# v3pow_2_4v7.net
KiCad netlist of a schematic drawn in EAGLE
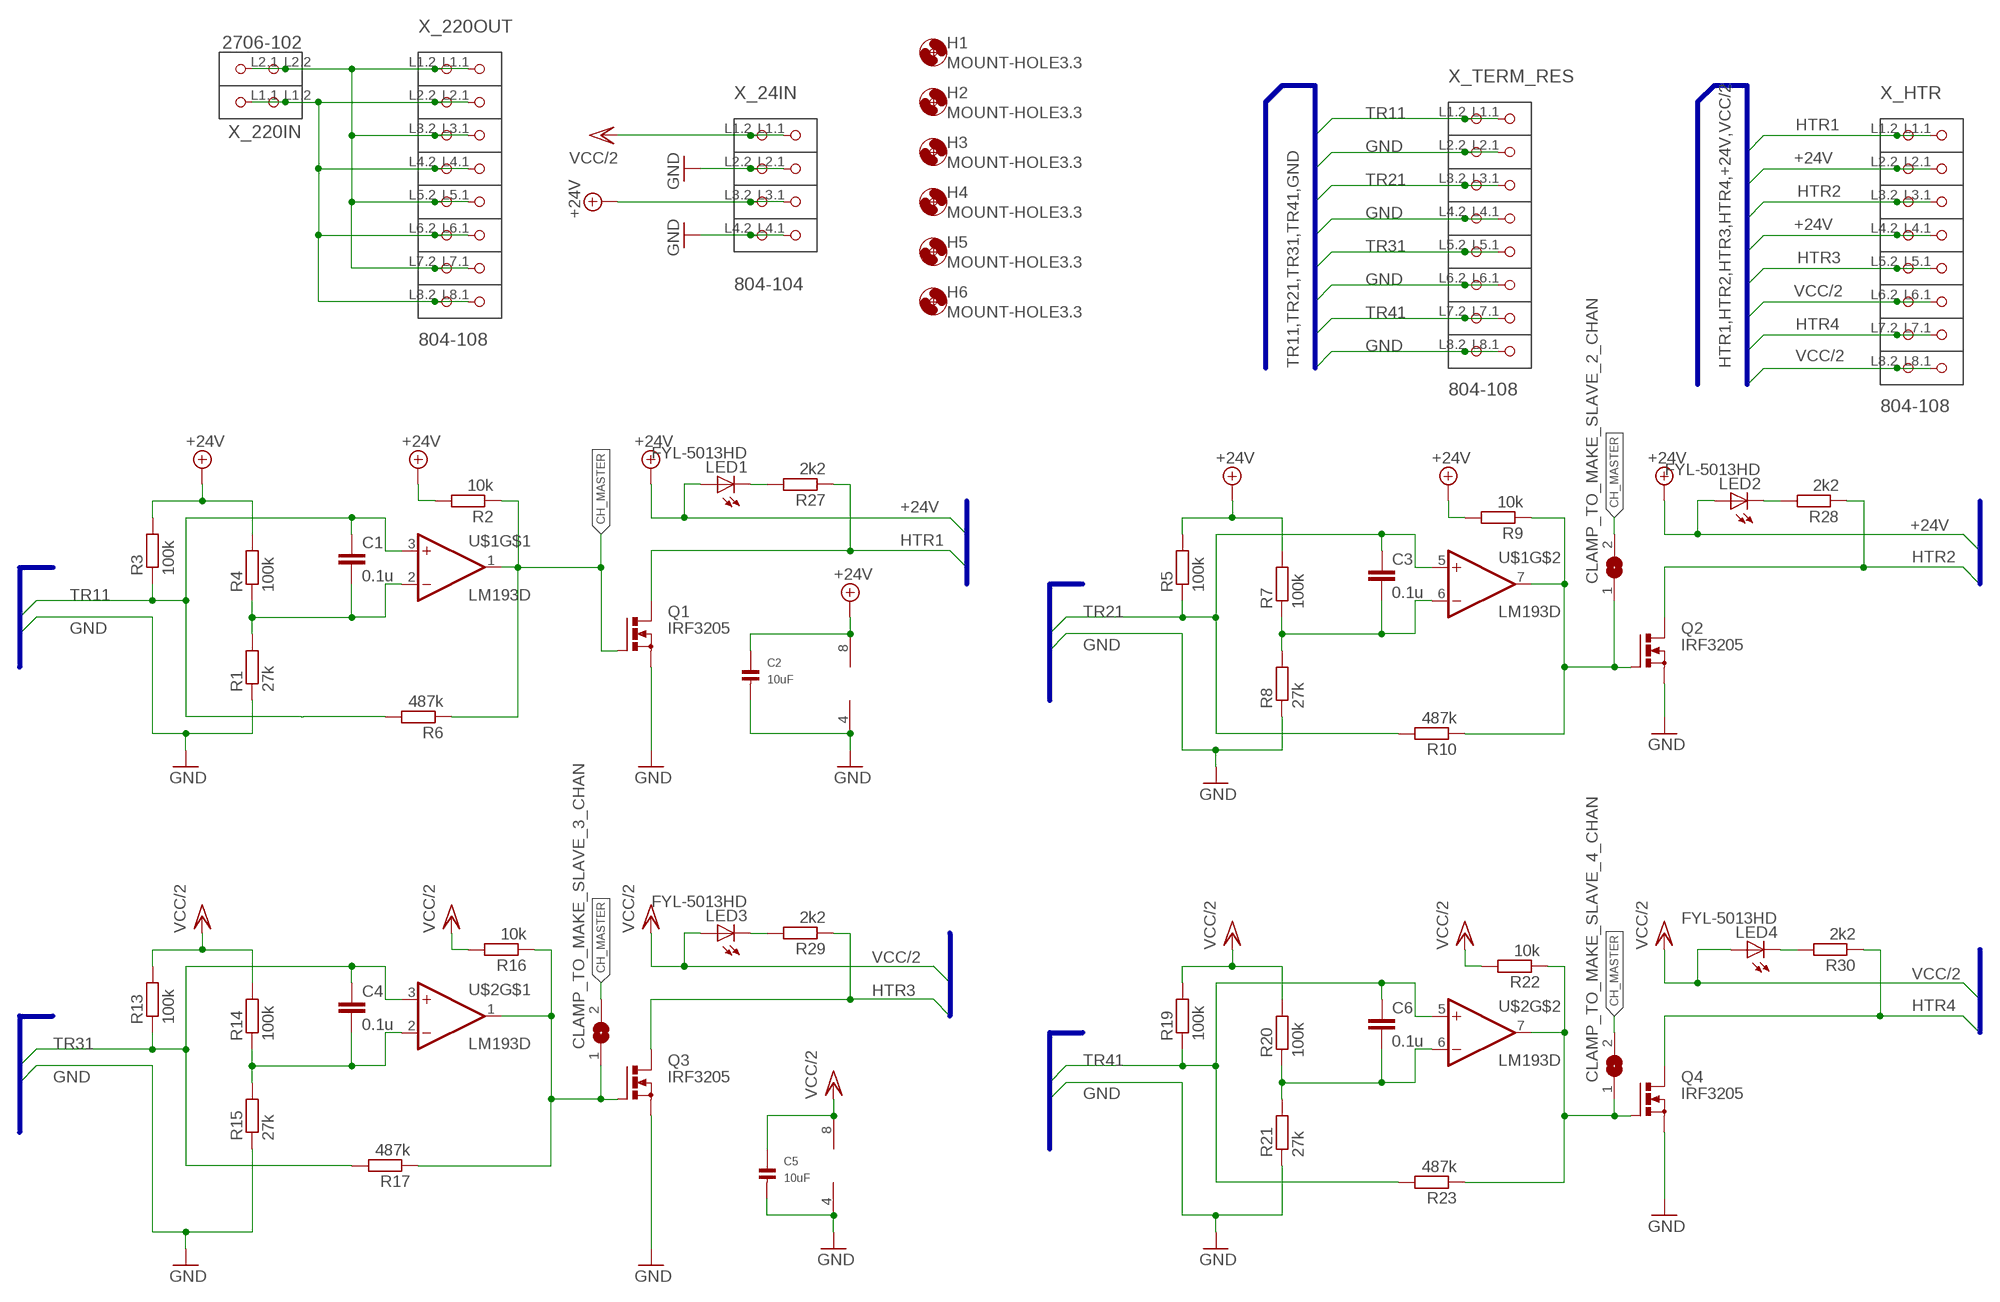
[diagram p0: schematic, sheet 1]

(export (version "E")
  (design (tool "Eeschema 10.0.6"))
  (components
    (comp (ref "C1")
      (value "0.1u")
      (footprint "eagle-import:C0805")
      (libsource (lib "eagle-import") (part "C-EUC0805"))
    )
    (comp (ref "C2")
      (value "10uF")
      (footprint "eagle-import:1206")
      (libsource (lib "eagle-import") (part "CAP_CERAMIC1206"))
    )
    (comp (ref "C3")
      (value "0.1u")
      (footprint "eagle-import:C0805")
      (libsource (lib "eagle-import") (part "C-EUC0805"))
    )
    (comp (ref "C4")
      (value "0.1u")
      (footprint "eagle-import:C0805")
      (libsource (lib "eagle-import") (part "C-EUC0805"))
    )
    (comp (ref "C5")
      (value "10uF")
      (footprint "eagle-import:1206")
      (libsource (lib "eagle-import") (part "CAP_CERAMIC1206"))
    )
    (comp (ref "C6")
      (value "0.1u")
      (footprint "eagle-import:C0805")
      (libsource (lib "eagle-import") (part "C-EUC0805"))
    )
    (comp (ref "CLAMP_TO_MAKE_SLAVE_2_CHAN")
      (value "SJ")
      (footprint "eagle-import:SJ")
      (libsource (lib "eagle-import") (part "SJ"))
    )
    (comp (ref "CLAMP_TO_MAKE_SLAVE_3_CHAN")
      (value "SJ")
      (footprint "eagle-import:SJ")
      (libsource (lib "eagle-import") (part "SJ"))
    )
    (comp (ref "CLAMP_TO_MAKE_SLAVE_4_CHAN")
      (value "SJ")
      (footprint "eagle-import:SJ")
      (libsource (lib "eagle-import") (part "SJ"))
    )
    (comp (ref "H1")
      (value "MOUNT-HOLE3.3")
      (footprint "eagle-import:3,3")
      (libsource (lib "eagle-import") (part "MOUNT-HOLE3.3"))
    )
    (comp (ref "H2")
      (value "MOUNT-HOLE3.3")
      (footprint "eagle-import:3,3")
      (libsource (lib "eagle-import") (part "MOUNT-HOLE3.3"))
    )
    (comp (ref "H3")
      (value "MOUNT-HOLE3.3")
      (footprint "eagle-import:3,3")
      (libsource (lib "eagle-import") (part "MOUNT-HOLE3.3"))
    )
    (comp (ref "H4")
      (value "MOUNT-HOLE3.3")
      (footprint "eagle-import:3,3")
      (libsource (lib "eagle-import") (part "MOUNT-HOLE3.3"))
    )
    (comp (ref "H5")
      (value "MOUNT-HOLE3.3")
      (footprint "eagle-import:3,3")
      (libsource (lib "eagle-import") (part "MOUNT-HOLE3.3"))
    )
    (comp (ref "H6")
      (value "MOUNT-HOLE3.3")
      (footprint "eagle-import:3,3")
      (libsource (lib "eagle-import") (part "MOUNT-HOLE3.3"))
    )
    (comp (ref "LED1")
      (value "FYL-5013HD")
      (footprint "eagle-import:LED5MM")
      (libsource (lib "eagle-import") (part "LED5MM"))
    )
    (comp (ref "LED2")
      (value "FYL-5013HD")
      (footprint "eagle-import:LED5MM")
      (libsource (lib "eagle-import") (part "LED5MM"))
    )
    (comp (ref "LED3")
      (value "FYL-5013HD")
      (footprint "eagle-import:LED5MM")
      (libsource (lib "eagle-import") (part "LED5MM"))
    )
    (comp (ref "LED4")
      (value "FYL-5013HD")
      (footprint "eagle-import:LED5MM")
      (libsource (lib "eagle-import") (part "LED5MM"))
    )
    (comp (ref "Q1")
      (value "IRF3205")
      (footprint "eagle-import:TO220BV")
      (libsource (lib "eagle-import") (part "PMOSFET_NTO220BV"))
    )
    (comp (ref "Q2")
      (value "IRF3205")
      (footprint "eagle-import:TO220BV")
      (libsource (lib "eagle-import") (part "PMOSFET_NTO220BV"))
    )
    (comp (ref "Q3")
      (value "IRF3205")
      (footprint "eagle-import:TO220BV")
      (libsource (lib "eagle-import") (part "PMOSFET_NTO220BV"))
    )
    (comp (ref "Q4")
      (value "IRF3205")
      (footprint "eagle-import:TO220BV")
      (libsource (lib "eagle-import") (part "PMOSFET_NTO220BV"))
    )
    (comp (ref "R1")
      (value "27k")
      (footprint "eagle-import:M0805")
      (libsource (lib "eagle-import") (part "R-EU_M0805"))
    )
    (comp (ref "R2")
      (value "10k")
      (footprint "eagle-import:M0805")
      (libsource (lib "eagle-import") (part "R-EU_M0805"))
    )
    (comp (ref "R3")
      (value "100k")
      (footprint "eagle-import:M0805")
      (libsource (lib "eagle-import") (part "R-EU_M0805"))
    )
    (comp (ref "R4")
      (value "100k")
      (footprint "eagle-import:M0805")
      (libsource (lib "eagle-import") (part "R-EU_M0805"))
    )
    (comp (ref "R5")
      (value "100k")
      (footprint "eagle-import:M0805")
      (libsource (lib "eagle-import") (part "R-EU_M0805"))
    )
    (comp (ref "R6")
      (value "487k")
      (footprint "eagle-import:M0805")
      (libsource (lib "eagle-import") (part "R-EU_M0805"))
    )
    (comp (ref "R7")
      (value "100k")
      (footprint "eagle-import:M0805")
      (libsource (lib "eagle-import") (part "R-EU_M0805"))
    )
    (comp (ref "R8")
      (value "27k")
      (footprint "eagle-import:M0805")
      (libsource (lib "eagle-import") (part "R-EU_M0805"))
    )
    (comp (ref "R9")
      (value "10k")
      (footprint "eagle-import:M0805")
      (libsource (lib "eagle-import") (part "R-EU_M0805"))
    )
    (comp (ref "R10")
      (value "487k")
      (footprint "eagle-import:M0805")
      (libsource (lib "eagle-import") (part "R-EU_M0805"))
    )
    (comp (ref "R13")
      (value "100k")
      (footprint "eagle-import:M0805")
      (libsource (lib "eagle-import") (part "R-EU_M0805"))
    )
    (comp (ref "R14")
      (value "100k")
      (footprint "eagle-import:M0805")
      (libsource (lib "eagle-import") (part "R-EU_M0805"))
    )
    (comp (ref "R15")
      (value "27k")
      (footprint "eagle-import:M0805")
      (libsource (lib "eagle-import") (part "R-EU_M0805"))
    )
    (comp (ref "R16")
      (value "10k")
      (footprint "eagle-import:M0805")
      (libsource (lib "eagle-import") (part "R-EU_M0805"))
    )
    (comp (ref "R17")
      (value "487k")
      (footprint "eagle-import:M0805")
      (libsource (lib "eagle-import") (part "R-EU_M0805"))
    )
    (comp (ref "R19")
      (value "100k")
      (footprint "eagle-import:M0805")
      (libsource (lib "eagle-import") (part "R-EU_M0805"))
    )
    (comp (ref "R20")
      (value "100k")
      (footprint "eagle-import:M0805")
      (libsource (lib "eagle-import") (part "R-EU_M0805"))
    )
    (comp (ref "R21")
      (value "27k")
      (footprint "eagle-import:M0805")
      (libsource (lib "eagle-import") (part "R-EU_M0805"))
    )
    (comp (ref "R22")
      (value "10k")
      (footprint "eagle-import:M0805")
      (libsource (lib "eagle-import") (part "R-EU_M0805"))
    )
    (comp (ref "R23")
      (value "487k")
      (footprint "eagle-import:M0805")
      (libsource (lib "eagle-import") (part "R-EU_M0805"))
    )
    (comp (ref "R27")
      (value "2k2")
      (footprint "eagle-import:M0805")
      (libsource (lib "eagle-import") (part "R-EU_M0805"))
    )
    (comp (ref "R28")
      (value "2k2")
      (footprint "eagle-import:M0805")
      (libsource (lib "eagle-import") (part "R-EU_M0805"))
    )
    (comp (ref "R29")
      (value "2k2")
      (footprint "eagle-import:M0805")
      (libsource (lib "eagle-import") (part "R-EU_M0805"))
    )
    (comp (ref "R30")
      (value "2k2")
      (footprint "eagle-import:M0805")
      (libsource (lib "eagle-import") (part "R-EU_M0805"))
    )
    (comp (ref "U$1")
      (value "LM193D")
      (footprint "eagle-import:SO08")
      (libsource (lib "eagle-import") (part "LM193D"))
    )
    (comp (ref "U$2")
      (value "LM193D")
      (footprint "eagle-import:SO08")
      (libsource (lib "eagle-import") (part "LM193D"))
    )
    (comp (ref "X_24IN")
      (value "804-104")
      (footprint "eagle-import:P-804-104")
      (libsource (lib "eagle-import") (part "804-104"))
    )
    (comp (ref "X_220IN")
      (value "2706-102")
      (footprint "eagle-import:P-2706-102")
      (libsource (lib "eagle-import") (part "2706-102"))
    )
    (comp (ref "X_220OUT")
      (value "804-108")
      (footprint "eagle-import:P-804-108")
      (libsource (lib "eagle-import") (part "804-108"))
    )
    (comp (ref "X_HTR")
      (value "804-108")
      (footprint "eagle-import:P-804-108")
      (libsource (lib "eagle-import") (part "804-108"))
    )
    (comp (ref "X_TERM_RES")
      (value "804-108")
      (footprint "eagle-import:P-804-108")
      (libsource (lib "eagle-import") (part "804-108"))
    )
  )
  (nets
    (net (code "5") (name "+24V") (class "Default")
      (node (ref "C2") (pin "1") (pinfunction "P$1_1") (pintype "passive"))
      (node (ref "LED1") (pin "A") (pinfunction "A_A") (pintype "passive"))
      (node (ref "LED2") (pin "A") (pinfunction "A_A") (pintype "passive"))
      (node (ref "R2") (pin "2") (pinfunction "2_2") (pintype "passive"))
      (node (ref "R3") (pin "2") (pinfunction "2_2") (pintype "passive"))
      (node (ref "R4") (pin "2") (pinfunction "2_2") (pintype "passive"))
      (node (ref "R5") (pin "2") (pinfunction "2_2") (pintype "passive"))
      (node (ref "R7") (pin "2") (pinfunction "2_2") (pintype "passive"))
      (node (ref "R9") (pin "2") (pinfunction "2_2") (pintype "passive"))
      (node (ref "U$1") (pin "8") (pinfunction "V+_8") (pintype "power_in"))
      (node (ref "X_24IN") (pin "L3.1") (pinfunction "P3.1_L3.1") (pintype "bidirectional"))
      (node (ref "X_24IN") (pin "L3.2") (pinfunction "P3.2_L3.2") (pintype "bidirectional"))
      (node (ref "X_HTR") (pin "L2.1") (pinfunction "P2.1_L2.1") (pintype "bidirectional"))
      (node (ref "X_HTR") (pin "L2.2") (pinfunction "P2.2_L2.2") (pintype "bidirectional"))
      (node (ref "X_HTR") (pin "L4.1") (pinfunction "P4.1_L4.1") (pintype "bidirectional"))
      (node (ref "X_HTR") (pin "L4.2") (pinfunction "P4.2_L4.2") (pintype "bidirectional"))
    )
    (net (code "6") (name "/HTR1") (class "Default")
      (node (ref "Q1") (pin "D") (pinfunction "D_D") (pintype "passive"))
      (node (ref "R27") (pin "1") (pinfunction "1_1") (pintype "passive"))
      (node (ref "X_HTR") (pin "L1.1") (pinfunction "P1.1_L1.1") (pintype "bidirectional"))
      (node (ref "X_HTR") (pin "L1.2") (pinfunction "P1.2_L1.2") (pintype "bidirectional"))
    )
    (net (code "7") (name "/HTR2") (class "Default")
      (node (ref "Q2") (pin "D") (pinfunction "D_D") (pintype "passive"))
      (node (ref "R28") (pin "1") (pinfunction "1_1") (pintype "passive"))
      (node (ref "X_HTR") (pin "L3.1") (pinfunction "P3.1_L3.1") (pintype "bidirectional"))
      (node (ref "X_HTR") (pin "L3.2") (pinfunction "P3.2_L3.2") (pintype "bidirectional"))
    )
    (net (code "8") (name "/HTR3") (class "Default")
      (node (ref "Q3") (pin "D") (pinfunction "D_D") (pintype "passive"))
      (node (ref "R29") (pin "1") (pinfunction "1_1") (pintype "passive"))
      (node (ref "X_HTR") (pin "L5.1") (pinfunction "P5.1_L5.1") (pintype "bidirectional"))
      (node (ref "X_HTR") (pin "L5.2") (pinfunction "P5.2_L5.2") (pintype "bidirectional"))
    )
    (net (code "9") (name "/HTR4") (class "Default")
      (node (ref "Q4") (pin "D") (pinfunction "D_D") (pintype "passive"))
      (node (ref "R30") (pin "1") (pinfunction "1_1") (pintype "passive"))
      (node (ref "X_HTR") (pin "L7.1") (pinfunction "P7.1_L7.1") (pintype "bidirectional"))
      (node (ref "X_HTR") (pin "L7.2") (pinfunction "P7.2_L7.2") (pintype "bidirectional"))
    )
    (net (code "10") (name "/TR11") (class "Default")
      (node (ref "C1") (pin "1") (pinfunction "1_1") (pintype "passive"))
      (node (ref "R3") (pin "1") (pinfunction "1_1") (pintype "passive"))
      (node (ref "R6") (pin "2") (pinfunction "2_2") (pintype "passive"))
      (node (ref "U$1") (pin "3") (pinfunction "+IN_3") (pintype "input"))
      (node (ref "X_TERM_RES") (pin "L1.1") (pinfunction "P1.1_L1.1") (pintype "bidirectional"))
      (node (ref "X_TERM_RES") (pin "L1.2") (pinfunction "P1.2_L1.2") (pintype "bidirectional"))
    )
    (net (code "11") (name "/TR21") (class "Default")
      (node (ref "C3") (pin "1") (pinfunction "1_1") (pintype "passive"))
      (node (ref "R10") (pin "2") (pinfunction "2_2") (pintype "passive"))
      (node (ref "R5") (pin "1") (pinfunction "1_1") (pintype "passive"))
      (node (ref "U$1") (pin "5") (pinfunction "+IN_5") (pintype "input"))
      (node (ref "X_TERM_RES") (pin "L3.1") (pinfunction "P3.1_L3.1") (pintype "bidirectional"))
      (node (ref "X_TERM_RES") (pin "L3.2") (pinfunction "P3.2_L3.2") (pintype "bidirectional"))
    )
    (net (code "12") (name "/TR31") (class "Default")
      (node (ref "C4") (pin "1") (pinfunction "1_1") (pintype "passive"))
      (node (ref "R13") (pin "1") (pinfunction "1_1") (pintype "passive"))
      (node (ref "R17") (pin "2") (pinfunction "2_2") (pintype "passive"))
      (node (ref "U$2") (pin "3") (pinfunction "+IN_3") (pintype "input"))
      (node (ref "X_TERM_RES") (pin "L5.1") (pinfunction "P5.1_L5.1") (pintype "bidirectional"))
      (node (ref "X_TERM_RES") (pin "L5.2") (pinfunction "P5.2_L5.2") (pintype "bidirectional"))
    )
    (net (code "13") (name "/TR41") (class "Default")
      (node (ref "C6") (pin "1") (pinfunction "1_1") (pintype "passive"))
      (node (ref "R19") (pin "1") (pinfunction "1_1") (pintype "passive"))
      (node (ref "R23") (pin "2") (pinfunction "2_2") (pintype "passive"))
      (node (ref "U$2") (pin "5") (pinfunction "+IN_5") (pintype "input"))
      (node (ref "X_TERM_RES") (pin "L7.1") (pinfunction "P7.1_L7.1") (pintype "bidirectional"))
      (node (ref "X_TERM_RES") (pin "L7.2") (pinfunction "P7.2_L7.2") (pintype "bidirectional"))
    )
    (net (code "17") (name "CH_MASTER") (class "Default")
      (node (ref "CLAMP_TO_MAKE_SLAVE_2_CHAN") (pin "2") (pinfunction "2_2") (pintype "passive"))
      (node (ref "CLAMP_TO_MAKE_SLAVE_3_CHAN") (pin "2") (pinfunction "2_2") (pintype "passive"))
      (node (ref "CLAMP_TO_MAKE_SLAVE_4_CHAN") (pin "2") (pinfunction "2_2") (pintype "passive"))
      (node (ref "Q1") (pin "G") (pinfunction "G_G") (pintype "passive"))
      (node (ref "R2") (pin "1") (pinfunction "1_1") (pintype "passive"))
      (node (ref "R6") (pin "1") (pinfunction "1_1") (pintype "passive"))
      (node (ref "U$1") (pin "1") (pinfunction "OUT_1") (pintype "output"))
    )
    (net (code "18") (name "GND") (class "Default")
      (node (ref "C2") (pin "2") (pinfunction "P$2_2") (pintype "passive"))
      (node (ref "C5") (pin "2") (pinfunction "P$2_2") (pintype "passive"))
      (node (ref "Q1") (pin "S") (pinfunction "S_S") (pintype "passive"))
      (node (ref "Q2") (pin "S") (pinfunction "S_S") (pintype "passive"))
      (node (ref "Q3") (pin "S") (pinfunction "S_S") (pintype "passive"))
      (node (ref "Q4") (pin "S") (pinfunction "S_S") (pintype "passive"))
      (node (ref "R1") (pin "1") (pinfunction "1_1") (pintype "passive"))
      (node (ref "R15") (pin "1") (pinfunction "1_1") (pintype "passive"))
      (node (ref "R21") (pin "1") (pinfunction "1_1") (pintype "passive"))
      (node (ref "R8") (pin "1") (pinfunction "1_1") (pintype "passive"))
      (node (ref "U$1") (pin "4") (pinfunction "V-_4") (pintype "power_in"))
      (node (ref "U$2") (pin "4") (pinfunction "V-_4") (pintype "power_in"))
      (node (ref "X_24IN") (pin "L2.1") (pinfunction "P2.1_L2.1") (pintype "bidirectional"))
      (node (ref "X_24IN") (pin "L2.2") (pinfunction "P2.2_L2.2") (pintype "bidirectional"))
      (node (ref "X_24IN") (pin "L4.1") (pinfunction "P4.1_L4.1") (pintype "bidirectional"))
      (node (ref "X_24IN") (pin "L4.2") (pinfunction "P4.2_L4.2") (pintype "bidirectional"))
      (node (ref "X_TERM_RES") (pin "L2.1") (pinfunction "P2.1_L2.1") (pintype "bidirectional"))
      (node (ref "X_TERM_RES") (pin "L2.2") (pinfunction "P2.2_L2.2") (pintype "bidirectional"))
      (node (ref "X_TERM_RES") (pin "L4.1") (pinfunction "P4.1_L4.1") (pintype "bidirectional"))
      (node (ref "X_TERM_RES") (pin "L4.2") (pinfunction "P4.2_L4.2") (pintype "bidirectional"))
      (node (ref "X_TERM_RES") (pin "L6.1") (pinfunction "P6.1_L6.1") (pintype "bidirectional"))
      (node (ref "X_TERM_RES") (pin "L6.2") (pinfunction "P6.2_L6.2") (pintype "bidirectional"))
      (node (ref "X_TERM_RES") (pin "L8.1") (pinfunction "P8.1_L8.1") (pintype "bidirectional"))
      (node (ref "X_TERM_RES") (pin "L8.2") (pinfunction "P8.2_L8.2") (pintype "bidirectional"))
    )
    (net (code "19") (name "Net-(LED1-C)") (class "Default")
      (node (ref "LED1") (pin "K") (pinfunction "C_K") (pintype "passive"))
      (node (ref "R27") (pin "2") (pinfunction "2_2") (pintype "passive"))
    )
    (net (code "20") (name "Net-(LED2-C)") (class "Default")
      (node (ref "LED2") (pin "K") (pinfunction "C_K") (pintype "passive"))
      (node (ref "R28") (pin "2") (pinfunction "2_2") (pintype "passive"))
    )
    (net (code "21") (name "Net-(LED3-C)") (class "Default")
      (node (ref "LED3") (pin "K") (pinfunction "C_K") (pintype "passive"))
      (node (ref "R29") (pin "2") (pinfunction "2_2") (pintype "passive"))
    )
    (net (code "22") (name "Net-(LED4-C)") (class "Default")
      (node (ref "LED4") (pin "K") (pinfunction "C_K") (pintype "passive"))
      (node (ref "R30") (pin "2") (pinfunction "2_2") (pintype "passive"))
    )
    (net (code "23") (name "Net-(U$1A--IN)") (class "Default")
      (node (ref "C1") (pin "2") (pinfunction "2_2") (pintype "passive"))
      (node (ref "R1") (pin "2") (pinfunction "2_2") (pintype "passive"))
      (node (ref "R4") (pin "1") (pinfunction "1_1") (pintype "passive"))
      (node (ref "U$1") (pin "2") (pinfunction "-IN_2") (pintype "input"))
    )
    (net (code "24") (name "Net-(U$1B--IN)") (class "Default")
      (node (ref "C3") (pin "2") (pinfunction "2_2") (pintype "passive"))
      (node (ref "R7") (pin "1") (pinfunction "1_1") (pintype "passive"))
      (node (ref "R8") (pin "2") (pinfunction "2_2") (pintype "passive"))
      (node (ref "U$1") (pin "6") (pinfunction "-IN_6") (pintype "input"))
    )
    (net (code "25") (name "Net-(U$1B-OUT)") (class "Default")
      (node (ref "CLAMP_TO_MAKE_SLAVE_2_CHAN") (pin "1") (pinfunction "1_1") (pintype "passive"))
      (node (ref "Q2") (pin "G") (pinfunction "G_G") (pintype "passive"))
      (node (ref "R10") (pin "1") (pinfunction "1_1") (pintype "passive"))
      (node (ref "R9") (pin "1") (pinfunction "1_1") (pintype "passive"))
      (node (ref "U$1") (pin "7") (pinfunction "OUT_7") (pintype "output"))
    )
    (net (code "26") (name "Net-(U$2A--IN)") (class "Default")
      (node (ref "C4") (pin "2") (pinfunction "2_2") (pintype "passive"))
      (node (ref "R14") (pin "1") (pinfunction "1_1") (pintype "passive"))
      (node (ref "R15") (pin "2") (pinfunction "2_2") (pintype "passive"))
      (node (ref "U$2") (pin "2") (pinfunction "-IN_2") (pintype "input"))
    )
    (net (code "27") (name "Net-(U$2A-OUT)") (class "Default")
      (node (ref "CLAMP_TO_MAKE_SLAVE_3_CHAN") (pin "1") (pinfunction "1_1") (pintype "passive"))
      (node (ref "Q3") (pin "G") (pinfunction "G_G") (pintype "passive"))
      (node (ref "R16") (pin "1") (pinfunction "1_1") (pintype "passive"))
      (node (ref "R17") (pin "1") (pinfunction "1_1") (pintype "passive"))
      (node (ref "U$2") (pin "1") (pinfunction "OUT_1") (pintype "output"))
    )
    (net (code "28") (name "Net-(U$2B--IN)") (class "Default")
      (node (ref "C6") (pin "2") (pinfunction "2_2") (pintype "passive"))
      (node (ref "R20") (pin "1") (pinfunction "1_1") (pintype "passive"))
      (node (ref "R21") (pin "2") (pinfunction "2_2") (pintype "passive"))
      (node (ref "U$2") (pin "6") (pinfunction "-IN_6") (pintype "input"))
    )
    (net (code "29") (name "Net-(U$2B-OUT)") (class "Default")
      (node (ref "CLAMP_TO_MAKE_SLAVE_4_CHAN") (pin "1") (pinfunction "1_1") (pintype "passive"))
      (node (ref "Q4") (pin "G") (pinfunction "G_G") (pintype "passive"))
      (node (ref "R22") (pin "1") (pinfunction "1_1") (pintype "passive"))
      (node (ref "R23") (pin "1") (pinfunction "1_1") (pintype "passive"))
      (node (ref "U$2") (pin "7") (pinfunction "OUT_7") (pintype "output"))
    )
    (net (code "30") (name "Net-(X_220IN-P1.1)") (class "Default")
      (node (ref "X_220IN") (pin "L1.1") (pinfunction "P1.1_L1.1") (pintype "bidirectional"))
      (node (ref "X_220IN") (pin "L1.2") (pinfunction "P1.2_L1.2") (pintype "bidirectional"))
      (node (ref "X_220OUT") (pin "L2.1") (pinfunction "P2.1_L2.1") (pintype "bidirectional"))
      (node (ref "X_220OUT") (pin "L2.2") (pinfunction "P2.2_L2.2") (pintype "bidirectional"))
      (node (ref "X_220OUT") (pin "L4.1") (pinfunction "P4.1_L4.1") (pintype "bidirectional"))
      (node (ref "X_220OUT") (pin "L4.2") (pinfunction "P4.2_L4.2") (pintype "bidirectional"))
      (node (ref "X_220OUT") (pin "L6.1") (pinfunction "P6.1_L6.1") (pintype "bidirectional"))
      (node (ref "X_220OUT") (pin "L6.2") (pinfunction "P6.2_L6.2") (pintype "bidirectional"))
      (node (ref "X_220OUT") (pin "L8.1") (pinfunction "P8.1_L8.1") (pintype "bidirectional"))
      (node (ref "X_220OUT") (pin "L8.2") (pinfunction "P8.2_L8.2") (pintype "bidirectional"))
    )
    (net (code "31") (name "Net-(X_220IN-P2.1)") (class "Default")
      (node (ref "X_220IN") (pin "L2.1") (pinfunction "P2.1_L2.1") (pintype "bidirectional"))
      (node (ref "X_220IN") (pin "L2.2") (pinfunction "P2.2_L2.2") (pintype "bidirectional"))
      (node (ref "X_220OUT") (pin "L1.1") (pinfunction "P1.1_L1.1") (pintype "bidirectional"))
      (node (ref "X_220OUT") (pin "L1.2") (pinfunction "P1.2_L1.2") (pintype "bidirectional"))
      (node (ref "X_220OUT") (pin "L3.1") (pinfunction "P3.1_L3.1") (pintype "bidirectional"))
      (node (ref "X_220OUT") (pin "L3.2") (pinfunction "P3.2_L3.2") (pintype "bidirectional"))
      (node (ref "X_220OUT") (pin "L5.1") (pinfunction "P5.1_L5.1") (pintype "bidirectional"))
      (node (ref "X_220OUT") (pin "L5.2") (pinfunction "P5.2_L5.2") (pintype "bidirectional"))
      (node (ref "X_220OUT") (pin "L7.1") (pinfunction "P7.1_L7.1") (pintype "bidirectional"))
      (node (ref "X_220OUT") (pin "L7.2") (pinfunction "P7.2_L7.2") (pintype "bidirectional"))
    )
    (net (code "32") (name "VCC{slash}2") (class "Default")
      (node (ref "C5") (pin "1") (pinfunction "P$1_1") (pintype "passive"))
      (node (ref "LED3") (pin "A") (pinfunction "A_A") (pintype "passive"))
      (node (ref "LED4") (pin "A") (pinfunction "A_A") (pintype "passive"))
      (node (ref "R13") (pin "2") (pinfunction "2_2") (pintype "passive"))
      (node (ref "R14") (pin "2") (pinfunction "2_2") (pintype "passive"))
      (node (ref "R16") (pin "2") (pinfunction "2_2") (pintype "passive"))
      (node (ref "R19") (pin "2") (pinfunction "2_2") (pintype "passive"))
      (node (ref "R20") (pin "2") (pinfunction "2_2") (pintype "passive"))
      (node (ref "R22") (pin "2") (pinfunction "2_2") (pintype "passive"))
      (node (ref "U$2") (pin "8") (pinfunction "V+_8") (pintype "power_in"))
      (node (ref "X_24IN") (pin "L1.1") (pinfunction "P1.1_L1.1") (pintype "bidirectional"))
      (node (ref "X_24IN") (pin "L1.2") (pinfunction "P1.2_L1.2") (pintype "bidirectional"))
      (node (ref "X_HTR") (pin "L6.1") (pinfunction "P6.1_L6.1") (pintype "bidirectional"))
      (node (ref "X_HTR") (pin "L6.2") (pinfunction "P6.2_L6.2") (pintype "bidirectional"))
      (node (ref "X_HTR") (pin "L8.1") (pinfunction "P8.1_L8.1") (pintype "bidirectional"))
      (node (ref "X_HTR") (pin "L8.2") (pinfunction "P8.2_L8.2") (pintype "bidirectional"))
    )
  )
)
